# 464511_002_3.net
KiCad netlist of a schematic drawn in Altium Designer
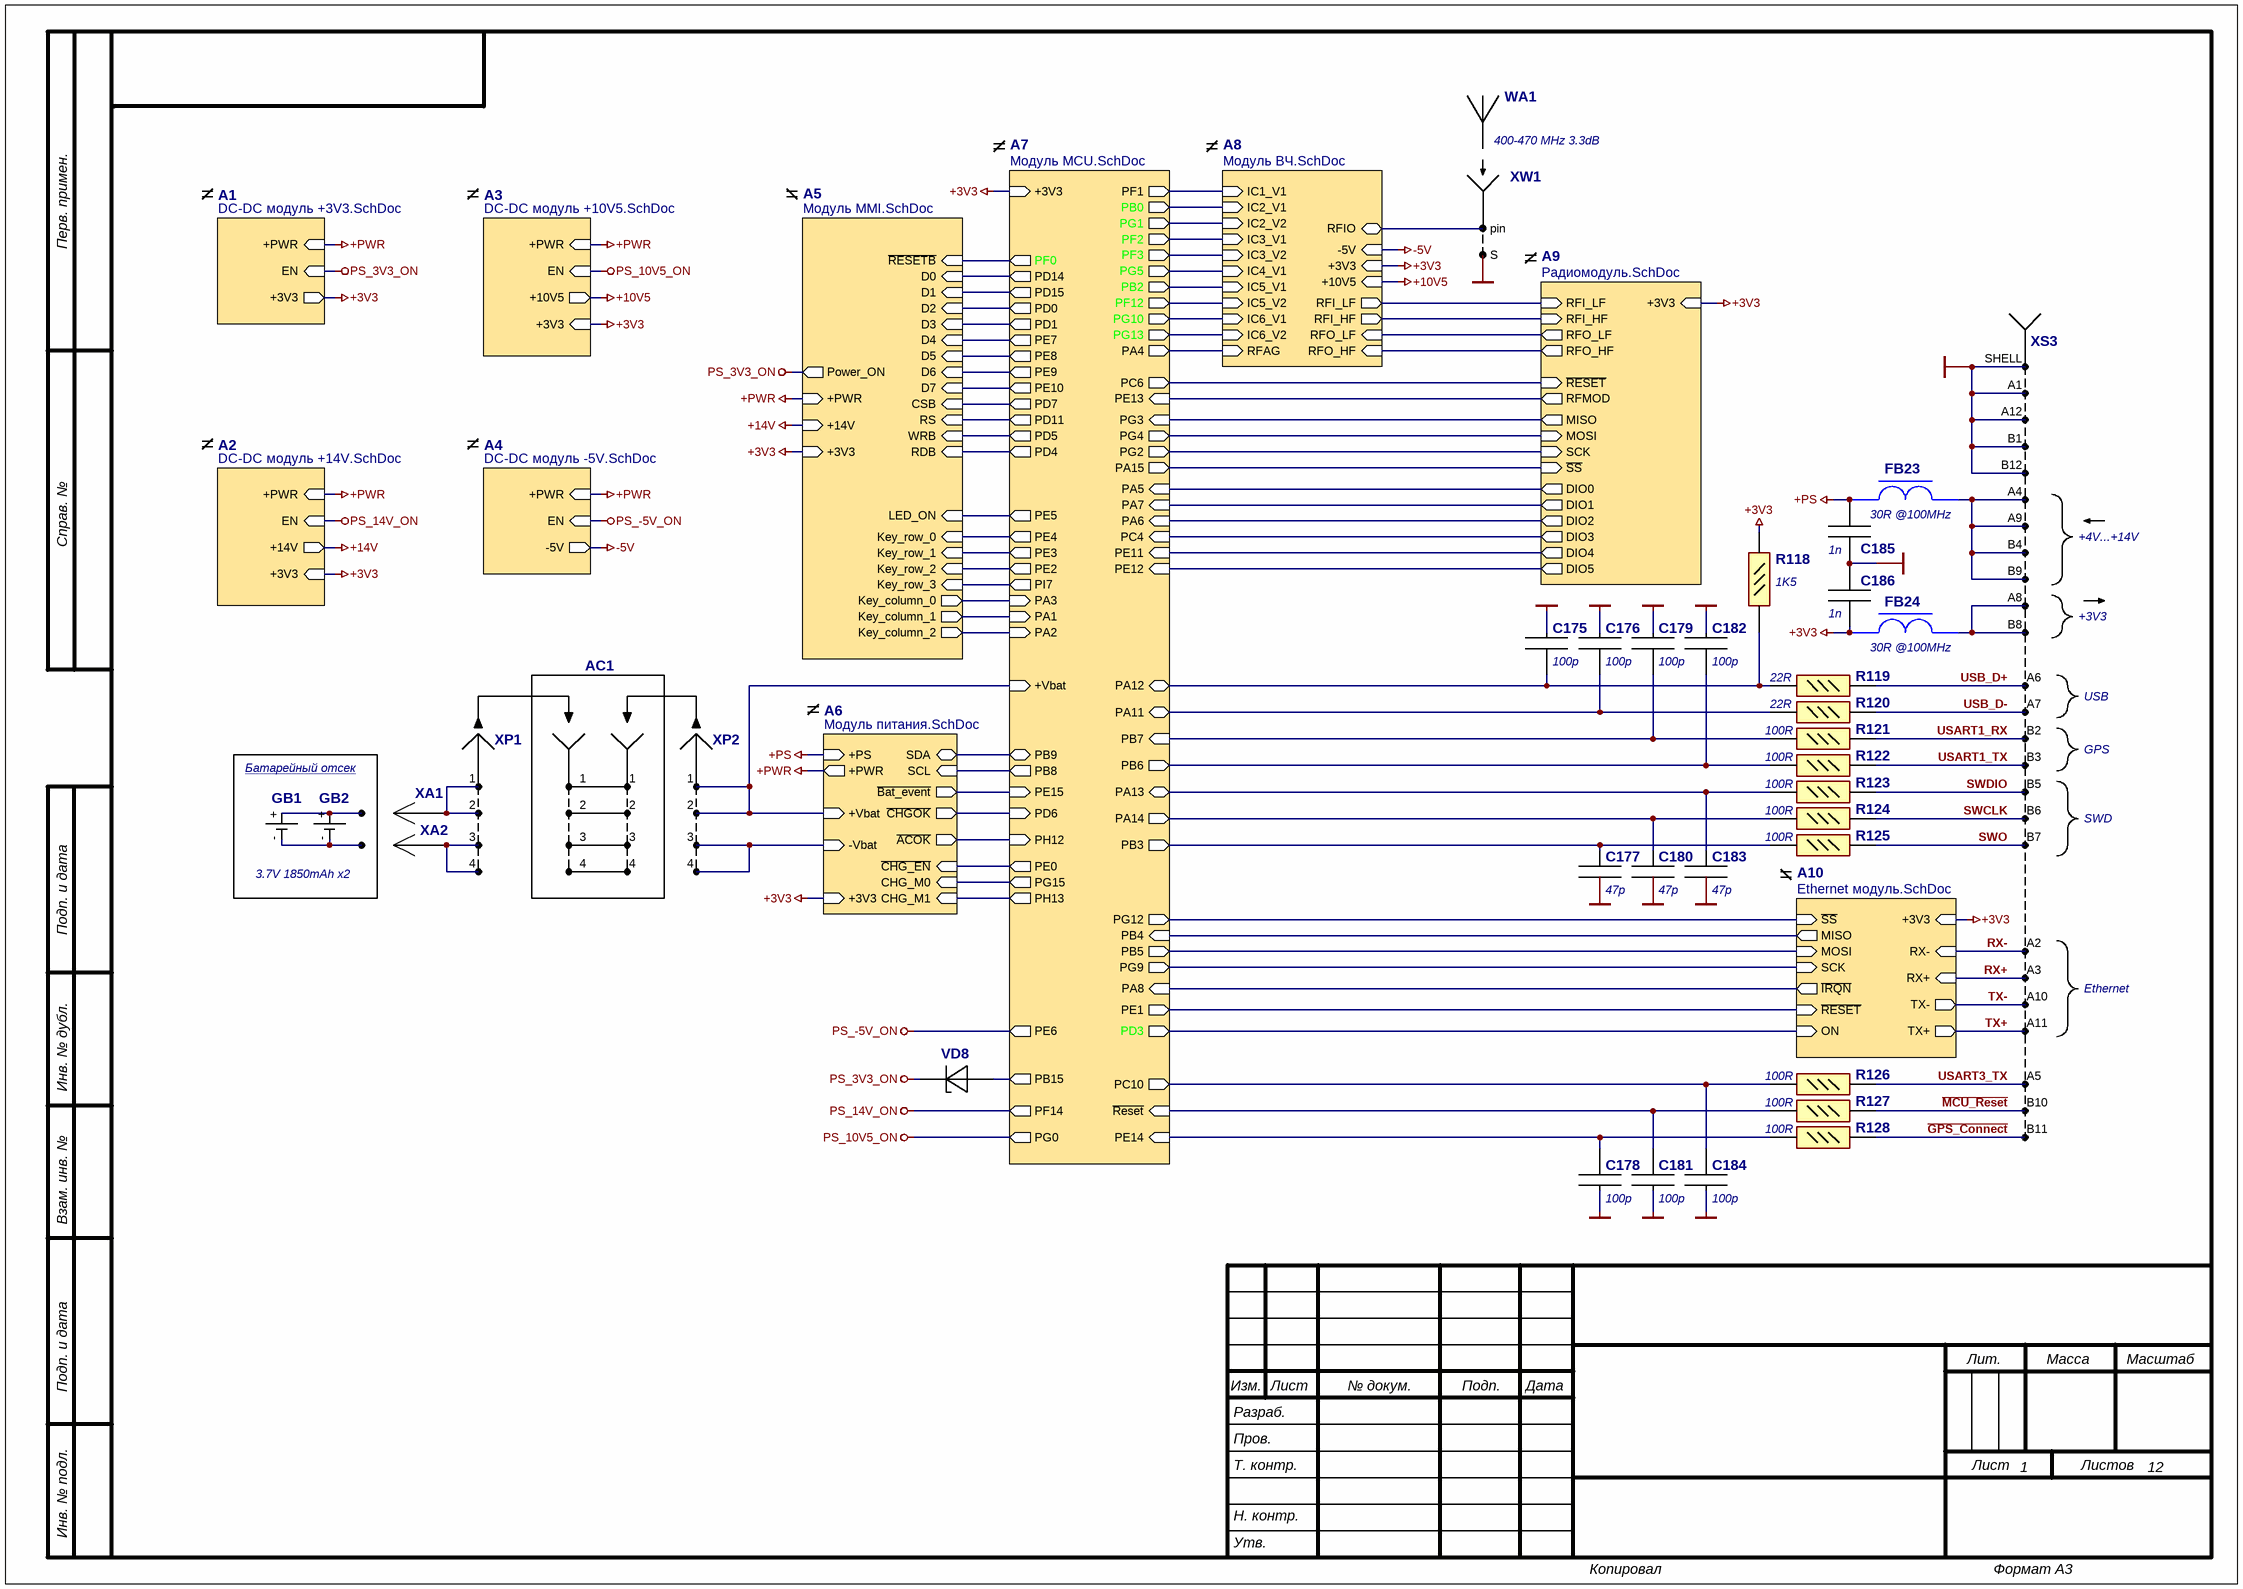
[diagram p0: ТЕИЯ.464511.002 Э3.SchDoc]

(export (version "E")
  (design (tool "Eeschema 10.0.6"))
  (components
    (comp (ref "AC1")
      (value "0151320401")
      (description "Cable-Assy Picolock 1.5mm Pitch 4 Wire 24AWG 100mm")
      (libsource (lib "Connectors") (part "0151320401"))
    )
    (comp (ref "C175")
      (value "100p")
      (footprint ":CAP0402 100x50x50")
      (description "CAP CER  50V C0G/NP0 0402")
      (fields (field (name "MANUFACTURER_PART_NUMBER") "GCM1555C1H101JA16D"))
      (libsource (lib "Capacitors 0402") (part "GCM1555C1H101JA16D"))
    )
    (comp (ref "C176")
      (value "100p")
      (footprint ":CAP0402 100x50x50")
      (description "CAP CER  50V C0G/NP0 0402")
      (fields (field (name "MANUFACTURER_PART_NUMBER") "GCM1555C1H101JA16D"))
      (libsource (lib "Capacitors 0402") (part "GCM1555C1H101JA16D"))
    )
    (comp (ref "C177")
      (value "47p")
      (footprint ":CAP0402 100x50x50")
      (description "CAP CER  50V C0G/NP0 0402")
      (fields (field (name "MANUFACTURER_PART_NUMBER") "GJM1555C1H470GB01D"))
      (libsource (lib "Capacitors 0402") (part "GJM1555C1H470GB01D"))
    )
    (comp (ref "C178")
      (value "100p")
      (footprint ":CAP0402 100x50x50")
      (description "CAP CER  50V C0G/NP0 0402")
      (fields (field (name "MANUFACTURER_PART_NUMBER") "GCM1555C1H101JA16D"))
      (libsource (lib "Capacitors 0402") (part "GCM1555C1H101JA16D"))
    )
    (comp (ref "C179")
      (value "100p")
      (footprint ":CAP0402 100x50x50")
      (description "CAP CER  50V C0G/NP0 0402")
      (fields (field (name "MANUFACTURER_PART_NUMBER") "GCM1555C1H101JA16D"))
      (libsource (lib "Capacitors 0402") (part "GCM1555C1H101JA16D"))
    )
    (comp (ref "C180")
      (value "47p")
      (footprint ":CAP0402 100x50x50")
      (description "CAP CER  50V C0G/NP0 0402")
      (fields (field (name "MANUFACTURER_PART_NUMBER") "GJM1555C1H470GB01D"))
      (libsource (lib "Capacitors 0402") (part "GJM1555C1H470GB01D"))
    )
    (comp (ref "C181")
      (value "100p")
      (footprint ":CAP0402 100x50x50")
      (description "CAP CER  50V C0G/NP0 0402")
      (fields (field (name "MANUFACTURER_PART_NUMBER") "GCM1555C1H101JA16D"))
      (libsource (lib "Capacitors 0402") (part "GCM1555C1H101JA16D"))
    )
    (comp (ref "C182")
      (value "100p")
      (footprint ":CAP0402 100x50x50")
      (description "CAP CER  50V C0G/NP0 0402")
      (fields (field (name "MANUFACTURER_PART_NUMBER") "GCM1555C1H101JA16D"))
      (libsource (lib "Capacitors 0402") (part "GCM1555C1H101JA16D"))
    )
    (comp (ref "C183")
      (value "47p")
      (footprint ":CAP0402 100x50x50")
      (description "CAP CER  50V C0G/NP0 0402")
      (fields (field (name "MANUFACTURER_PART_NUMBER") "GJM1555C1H470GB01D"))
      (libsource (lib "Capacitors 0402") (part "GJM1555C1H470GB01D"))
    )
    (comp (ref "C184")
      (value "100p")
      (footprint ":CAP0402 100x50x50")
      (description "CAP CER  50V C0G/NP0 0402")
      (fields (field (name "MANUFACTURER_PART_NUMBER") "GCM1555C1H101JA16D"))
      (libsource (lib "Capacitors 0402") (part "GCM1555C1H101JA16D"))
    )
    (comp (ref "C185")
      (value "1n")
      (footprint ":CAP0402 100x50x50")
      (description "±5% 50V Ceramic Capacitor C0G, NP0 0402 (1005 Metric)")
      (fields (field (name "MANUFACTURER_PART_NUMBER") "GRM1555C1H102JA01J"))
      (libsource (lib "Capacitors 0402") (part "GRM1555C1H102JA01J"))
    )
    (comp (ref "C186")
      (value "1n")
      (footprint ":CAP0402 100x50x50")
      (description "±5% 50V Ceramic Capacitor C0G, NP0 0402 (1005 Metric)")
      (fields (field (name "MANUFACTURER_PART_NUMBER") "GRM1555C1H102JA01J"))
      (libsource (lib "Capacitors 0402") (part "GRM1555C1H102JA01J"))
    )
    (comp (ref "FB23")
      (value "30R @100MHz")
      (footprint ":FER BLM18SP300SN1D")
      (description "30 Ohms @ 100MHz 1 Power Line Ferrite Bead 0603 (1608 Metric) 6A 8mOhm")
      (fields
        (field (name "MANUFACTURER_PART_NUMBER") "BLM18SP300SN1D")
        (field (name "MOUSER PART NUMBER") "81-BLM18SP300SN1D")
      )
      (libsource (lib "Ferrite Bead") (part "BLM18SP300SN1D"))
    )
    (comp (ref "FB24")
      (value "30R @100MHz")
      (footprint ":FER BLM18SP300SN1D")
      (description "30 Ohms @ 100MHz 1 Power Line Ferrite Bead 0603 (1608 Metric) 6A 8mOhm")
      (fields
        (field (name "MANUFACTURER_PART_NUMBER") "BLM18SP300SN1D")
        (field (name "MOUSER PART NUMBER") "81-BLM18SP300SN1D")
      )
      (libsource (lib "Ferrite Bead") (part "BLM18SP300SN1D"))
    )
    (comp (ref "GB1")
      (value "3.7V 1850mAh")
      (description "Battery Li-po 3.7V 1850mAh 10х34х50")
      (fields (field (name "MANUFACTURER_PART_NUMBER") "LP-1850-103450UN"))
      (libsource (lib "Other") (part "LP-1850-103450UN"))
    )
    (comp (ref "GB2")
      (value "3.7V 1850mAh")
      (description "Battery Li-po 3.7V 1850mAh 10х34х50")
      (fields (field (name "MANUFACTURER_PART_NUMBER") "LP-1850-103450UN"))
      (libsource (lib "Other") (part "LP-1850-103450UN"))
    )
    (comp (ref "R118")
      (value "RC0402FR-07")
      (footprint ":RES0402")
      (fields (field (name "MANUFACTURER_PART_NUMBER (PART 2: VALUE)") "1K5"))
      (libsource (lib "") (part "RC0402FR-07_1"))
    )
    (comp (ref "R119")
      (value "RC0402FR-07")
      (footprint ":RES0402")
      (fields (field (name "MANUFACTURER_PART_NUMBER (PART 2: VALUE)") "22R"))
      (libsource (lib "Resistors 0402") (part "RC0402FR-07"))
    )
    (comp (ref "R120")
      (value "RC0402FR-07")
      (footprint ":RES0402")
      (fields (field (name "MANUFACTURER_PART_NUMBER (PART 2: VALUE)") "22R"))
      (libsource (lib "Resistors 0402") (part "RC0402FR-07"))
    )
    (comp (ref "R121")
      (value "RC0402FR-07")
      (footprint ":RES0402")
      (fields (field (name "MANUFACTURER_PART_NUMBER (PART 2: VALUE)") "100R"))
      (libsource (lib "Resistors 0402") (part "RC0402FR-07"))
    )
    (comp (ref "R122")
      (value "RC0402FR-07")
      (footprint ":RES0402")
      (fields (field (name "MANUFACTURER_PART_NUMBER (PART 2: VALUE)") "100R"))
      (libsource (lib "Resistors 0402") (part "RC0402FR-07"))
    )
    (comp (ref "R123")
      (value "RC0402FR-07")
      (footprint ":RES0402")
      (fields (field (name "MANUFACTURER_PART_NUMBER (PART 2: VALUE)") "100R"))
      (libsource (lib "Resistors 0402") (part "RC0402FR-07"))
    )
    (comp (ref "R124")
      (value "RC0402FR-07")
      (footprint ":RES0402")
      (fields (field (name "MANUFACTURER_PART_NUMBER (PART 2: VALUE)") "100R"))
      (libsource (lib "Resistors 0402") (part "RC0402FR-07"))
    )
    (comp (ref "R125")
      (value "RC0402FR-07")
      (footprint ":RES0402")
      (fields (field (name "MANUFACTURER_PART_NUMBER (PART 2: VALUE)") "100R"))
      (libsource (lib "Resistors 0402") (part "RC0402FR-07"))
    )
    (comp (ref "R126")
      (value "RC0402FR-07")
      (footprint ":RES0402")
      (fields (field (name "MANUFACTURER_PART_NUMBER (PART 2: VALUE)") "100R"))
      (libsource (lib "Resistors 0402") (part "RC0402FR-07"))
    )
    (comp (ref "R127")
      (value "RC0402FR-07")
      (footprint ":RES0402")
      (fields (field (name "MANUFACTURER_PART_NUMBER (PART 2: VALUE)") "100R"))
      (libsource (lib "Resistors 0402") (part "RC0402FR-07"))
    )
    (comp (ref "R128")
      (value "RC0402FR-07")
      (footprint ":RES0402")
      (fields (field (name "MANUFACTURER_PART_NUMBER (PART 2: VALUE)") "100R"))
      (libsource (lib "Resistors 0402") (part "RC0402FR-07"))
    )
    (comp (ref "VD8")
      (value "30V 0.1A")
      (footprint ":DIODE SOD-923F")
      (description "Diodes Schottky 0402 30V 0.1A")
      (fields
        (field (name "MANUFACTURER_PART_NUMBER") "CDBQR0130R")
        (field (name "MOUSER PART NUMBER") "750-CDBQR0130R")
      )
      (libsource (lib "Diodes 0402") (part "CDBQR0130R"))
    )
    (comp (ref "WA1")
      (value "ANT-433-CW-QW-SMA-male")
      (description "Antenna 400-470MHz 3.3dB SMA male")
      (fields (field (name "SHORT DESCRIPTION") "400-470 MHz 3.3dB"))
      (libsource (lib "Antennas") (part "ANT-433-CW-QW-SMA-male"))
    )
    (comp (ref "X2")
      (value "Big Circle Pad")
      (description "Большая круглая контактная площадка")
      (libsource (lib "Connectors") (part "Big Circle Pad"))
    )
    (comp (ref "X3")
      (value "Big Circle Pad")
      (description "Большая круглая контактная площадка")
      (libsource (lib "Connectors") (part "Big Circle Pad"))
    )
    (comp (ref "XA1")
      (value "0861-0-15-20-82-14-11-0")
      (description "Контакт пружинный 9A 10mm")
      (libsource (lib "Connectors") (part "0861-0-15-20-82-14-11-0"))
    )
    (comp (ref "XA2")
      (value "0861-0-15-20-82-14-11-0")
      (description "Контакт пружинный 9A 10mm")
      (libsource (lib "Connectors") (part "0861-0-15-20-82-14-11-0"))
    )
    (comp (ref "XP1")
      (value "5040500491")
      (footprint ":CON 5040500491")
      (description "Picolock 1.5mm Pitch Male 4-pin")
      (libsource (lib "Connectors") (part "5040500491"))
    )
    (comp (ref "XP2")
      (value "5040500491")
      (footprint ":CON 5040500491")
      (description "Picolock 1.5mm Pitch Male 4-pin")
      (libsource (lib "Connectors") (part "5040500491"))
    )
    (comp (ref "XS3")
      (value "UJ31-CH-3-MSMT-TR-67")
      (footprint ":CON TYPE-C UJ31-CH-3-MSMT-TR-67")
      (description "type C IP67 with ruber O ring")
      (libsource (lib "Connectors") (part "UJ31-CH-3-MSMT-TR-67"))
    )
    (comp (ref "XW1")
      (value "132371")
      (footprint ":CON 132371")
      (description "RF SMA Connectors 50Ohm")
      (libsource (lib "Connectors") (part "132371"))
    )
  )
  (nets
    (net (code "1") (name "+3V3") (class "Default")
      (node (ref "C186") (pin "2") (pinfunction "2_2") (pintype "passive"))
      (node (ref "FB24") (pin "1") (pinfunction "1_1") (pintype "passive"))
      (node (ref "R118") (pin "2") (pinfunction "2_2") (pintype "passive"))
    )
    (net (code "4") (name "+PS") (class "Default")
      (node (ref "C185") (pin "1") (pinfunction "1_1") (pintype "passive"))
      (node (ref "FB23") (pin "1") (pinfunction "1_1") (pintype "passive"))
    )
    (net (code "7") (name "/+Vbat") (class "Default")
      (node (ref "XP2") (pin "1") (pinfunction "1_1") (pintype "passive"))
      (node (ref "XP2") (pin "2") (pinfunction "2_2") (pintype "passive"))
    )
    (net (code "8") (name "/-Vbat") (class "Default")
      (node (ref "XP2") (pin "3") (pinfunction "3_3") (pintype "passive"))
      (node (ref "XP2") (pin "4") (pinfunction "4_4") (pintype "passive"))
    )
    (net (code "21") (name "/PA11") (class "Default")
      (node (ref "C176") (pin "1") (pinfunction "1_1") (pintype "passive"))
      (node (ref "R120") (pin "1") (pinfunction "1_1") (pintype "passive"))
    )
    (net (code "22") (name "/PA12") (class "Default")
      (node (ref "C175") (pin "1") (pinfunction "1_1") (pintype "passive"))
      (node (ref "R118") (pin "1") (pinfunction "1_1") (pintype "passive"))
      (node (ref "R119") (pin "1") (pinfunction "1_1") (pintype "passive"))
    )
    (net (code "23") (name "/PA13") (class "Default")
      (node (ref "C183") (pin "1") (pinfunction "1_1") (pintype "passive"))
      (node (ref "R123") (pin "1") (pinfunction "1_1") (pintype "passive"))
    )
    (net (code "24") (name "/PA14") (class "Default")
      (node (ref "C180") (pin "1") (pinfunction "1_1") (pintype "passive"))
      (node (ref "R124") (pin "1") (pinfunction "1_1") (pintype "passive"))
    )
    (net (code "28") (name "/PB3") (class "Default")
      (node (ref "C177") (pin "1") (pinfunction "1_1") (pintype "passive"))
      (node (ref "R125") (pin "1") (pinfunction "1_1") (pintype "passive"))
    )
    (net (code "30") (name "/PB6") (class "Default")
      (node (ref "C182") (pin "1") (pinfunction "1_1") (pintype "passive"))
      (node (ref "R122") (pin "1") (pinfunction "1_1") (pintype "passive"))
    )
    (net (code "31") (name "/PB7") (class "Default")
      (node (ref "C179") (pin "1") (pinfunction "1_1") (pintype "passive"))
      (node (ref "R121") (pin "1") (pinfunction "1_1") (pintype "passive"))
    )
    (net (code "34") (name "/PB15") (class "Default")
      (node (ref "VD8") (pin "2") (pinfunction "A_2") (pintype "passive"))
    )
    (net (code "36") (name "/PC10") (class "Default")
      (node (ref "C184") (pin "1") (pinfunction "1_1") (pintype "passive"))
      (node (ref "R126") (pin "1") (pinfunction "1_1") (pintype "passive"))
    )
    (net (code "56") (name "/PE14") (class "Default")
      (node (ref "C178") (pin "1") (pinfunction "1_1") (pintype "passive"))
      (node (ref "R128") (pin "1") (pinfunction "1_1") (pintype "passive"))
    )
    (net (code "73") (name "/RFIO") (class "Default")
      (node (ref "XW1") (pin "1") (pinfunction "pin_1") (pintype "passive"))
    )
    (net (code "79") (name "/RX+") (class "Default")
      (node (ref "XS3") (pin "A3") (pinfunction "SSTXN1_A3") (pintype "passive"))
    )
    (net (code "80") (name "/RX-") (class "Default")
      (node (ref "XS3") (pin "A2") (pinfunction "SSTXP1_A2") (pintype "passive"))
    )
    (net (code "81") (name "/SWCLK") (class "Default")
      (node (ref "R124") (pin "2") (pinfunction "2_2") (pintype "passive"))
      (node (ref "XS3") (pin "B6") (pinfunction "DP2_B6") (pintype "passive"))
    )
    (net (code "82") (name "/SWDIO") (class "Default")
      (node (ref "R123") (pin "2") (pinfunction "2_2") (pintype "passive"))
      (node (ref "XS3") (pin "B5") (pinfunction "CC2_B5") (pintype "passive"))
    )
    (net (code "83") (name "/SWO") (class "Default")
      (node (ref "R125") (pin "2") (pinfunction "2_2") (pintype "passive"))
      (node (ref "XS3") (pin "B7") (pinfunction "DN2_B7") (pintype "passive"))
    )
    (net (code "84") (name "/TX+") (class "Default")
      (node (ref "XS3") (pin "A11") (pinfunction "SSRXP2_A11") (pintype "passive"))
    )
    (net (code "85") (name "/TX-") (class "Default")
      (node (ref "XS3") (pin "A10") (pinfunction "SSRXN2_A10") (pintype "passive"))
    )
    (net (code "86") (name "/USART1_RX") (class "Default")
      (node (ref "R121") (pin "2") (pinfunction "2_2") (pintype "passive"))
      (node (ref "XS3") (pin "B2") (pinfunction "SSTXP2_B2") (pintype "passive"))
    )
    (net (code "87") (name "/USART1_TX") (class "Default")
      (node (ref "R122") (pin "2") (pinfunction "2_2") (pintype "passive"))
      (node (ref "XS3") (pin "B3") (pinfunction "SSTXN2_B3") (pintype "passive"))
    )
    (net (code "88") (name "/USART3_TX") (class "Default")
      (node (ref "R126") (pin "2") (pinfunction "2_2") (pintype "passive"))
      (node (ref "XS3") (pin "A5") (pinfunction "CC1_A5") (pintype "passive"))
    )
    (net (code "89") (name "/USB_D+") (class "Default")
      (node (ref "R119") (pin "2") (pinfunction "2_2") (pintype "passive"))
      (node (ref "XS3") (pin "A6") (pinfunction "DP1_A6") (pintype "passive"))
    )
    (net (code "90") (name "/USB_D-") (class "Default")
      (node (ref "R120") (pin "2") (pinfunction "2_2") (pintype "passive"))
      (node (ref "XS3") (pin "A7") (pinfunction "DN1_A7") (pintype "passive"))
    )
    (net (code "94") (name "/~{GPS_Connect}") (class "Default")
      (node (ref "R128") (pin "2") (pinfunction "2_2") (pintype "passive"))
      (node (ref "XS3") (pin "B11") (pinfunction "SSRXP1_B11") (pintype "passive"))
    )
    (net (code "96") (name "/~{MCU_Reset}") (class "Default")
      (node (ref "R127") (pin "2") (pinfunction "2_2") (pintype "passive"))
      (node (ref "XS3") (pin "B10") (pinfunction "SSRXN1_B10") (pintype "passive"))
    )
    (net (code "97") (name "/~{Reset}") (class "Default")
      (node (ref "C181") (pin "1") (pinfunction "1_1") (pintype "passive"))
      (node (ref "R127") (pin "1") (pinfunction "1_1") (pintype "passive"))
    )
    (net (code "98") (name "GND") (class "Default")
      (node (ref "C175") (pin "2") (pinfunction "2_2") (pintype "passive"))
      (node (ref "C176") (pin "2") (pinfunction "2_2") (pintype "passive"))
      (node (ref "C177") (pin "2") (pinfunction "2_2") (pintype "passive"))
      (node (ref "C178") (pin "2") (pinfunction "2_2") (pintype "passive"))
      (node (ref "C179") (pin "2") (pinfunction "2_2") (pintype "passive"))
      (node (ref "C180") (pin "2") (pinfunction "2_2") (pintype "passive"))
      (node (ref "C181") (pin "2") (pinfunction "2_2") (pintype "passive"))
      (node (ref "C182") (pin "2") (pinfunction "2_2") (pintype "passive"))
      (node (ref "C183") (pin "2") (pinfunction "2_2") (pintype "passive"))
      (node (ref "C184") (pin "2") (pinfunction "2_2") (pintype "passive"))
      (node (ref "C185") (pin "2") (pinfunction "2_2") (pintype "passive"))
      (node (ref "C186") (pin "1") (pinfunction "1_1") (pintype "passive"))
      (node (ref "XS3") (pin "A1") (pinfunction "GND_1_A1") (pintype "passive"))
      (node (ref "XS3") (pin "A12") (pinfunction "GND_2_A12") (pintype "passive"))
      (node (ref "XS3") (pin "B1") (pinfunction "GND_3_B1") (pintype "passive"))
      (node (ref "XS3") (pin "B12") (pinfunction "GND_4_B12") (pintype "passive"))
      (node (ref "XS3") (pin "SHELL") (pinfunction "SHELL_SHELL") (pintype "passive"))
      (node (ref "XW1") (pin "2") (pinfunction "S_2") (pintype "passive"))
    )
    (net (code "99") (name "Net-(GB1-black)") (class "Default")
      (node (ref "GB1") (pin "-") (pinfunction "black_-") (pintype "passive"))
      (node (ref "GB2") (pin "-") (pinfunction "black_-") (pintype "passive"))
      (node (ref "X3") (pin "1") (pinfunction "1_1") (pintype "passive"))
    )
    (net (code "100") (name "Net-(GB1-red)") (class "Default")
      (node (ref "GB1") (pin "+") (pinfunction "red_+") (pintype "passive"))
      (node (ref "GB2") (pin "+") (pinfunction "red_+") (pintype "passive"))
      (node (ref "X2") (pin "1") (pinfunction "1_1") (pintype "passive"))
    )
    (net (code "101") (name "Net-(XA1-Pad1)") (class "Default")
      (node (ref "XA1") (pin "1") (pinfunction "1_1") (pintype "passive"))
      (node (ref "XP1") (pin "1") (pinfunction "1_1") (pintype "passive"))
      (node (ref "XP1") (pin "2") (pinfunction "2_2") (pintype "passive"))
    )
    (net (code "102") (name "Net-(XA2-Pad1)") (class "Default")
      (node (ref "XA2") (pin "1") (pinfunction "1_1") (pintype "passive"))
      (node (ref "XP1") (pin "3") (pinfunction "3_3") (pintype "passive"))
      (node (ref "XP1") (pin "4") (pinfunction "4_4") (pintype "passive"))
    )
    (net (code "103") (name "Net-(XS3-SBU1)") (class "Default")
      (node (ref "FB24") (pin "2") (pinfunction "2_2") (pintype "passive"))
      (node (ref "XS3") (pin "A8") (pinfunction "SBU1_A8") (pintype "passive"))
      (node (ref "XS3") (pin "B8") (pinfunction "SBU2_B8") (pintype "passive"))
    )
    (net (code "104") (name "Net-(XS3-VBUS_1)") (class "Default")
      (node (ref "FB23") (pin "2") (pinfunction "2_2") (pintype "passive"))
      (node (ref "XS3") (pin "A4") (pinfunction "VBUS_1_A4") (pintype "passive"))
      (node (ref "XS3") (pin "A9") (pinfunction "VBUS_2_A9") (pintype "passive"))
      (node (ref "XS3") (pin "B4") (pinfunction "VBUS_3_B4") (pintype "passive"))
      (node (ref "XS3") (pin "B9") (pinfunction "VBUS_4_B9") (pintype "passive"))
    )
    (net (code "106") (name "PS_3V3_ON") (class "Default")
      (node (ref "VD8") (pin "1") (pinfunction "K_1") (pintype "passive"))
    )
    (net (code "109") (name "unconnected-(AC1-Pad1)") (class "Default")
      (node (ref "AC1") (pin "1") (pinfunction "1_1") (pintype "passive"))
    )
    (net (code "110") (name "unconnected-(AC1-Pad2)") (class "Default")
      (node (ref "AC1") (pin "2") (pinfunction "2_2") (pintype "passive"))
    )
    (net (code "111") (name "unconnected-(AC1-Pad3)") (class "Default")
      (node (ref "AC1") (pin "3") (pinfunction "3_3") (pintype "passive"))
    )
    (net (code "112") (name "unconnected-(AC1-Pad4)") (class "Default")
      (node (ref "AC1") (pin "4") (pinfunction "4_4") (pintype "passive"))
    )
  )
)
